# DisplayAddOn_V02-010.net
KiCad netlist of a schematic drawn in EAGLE
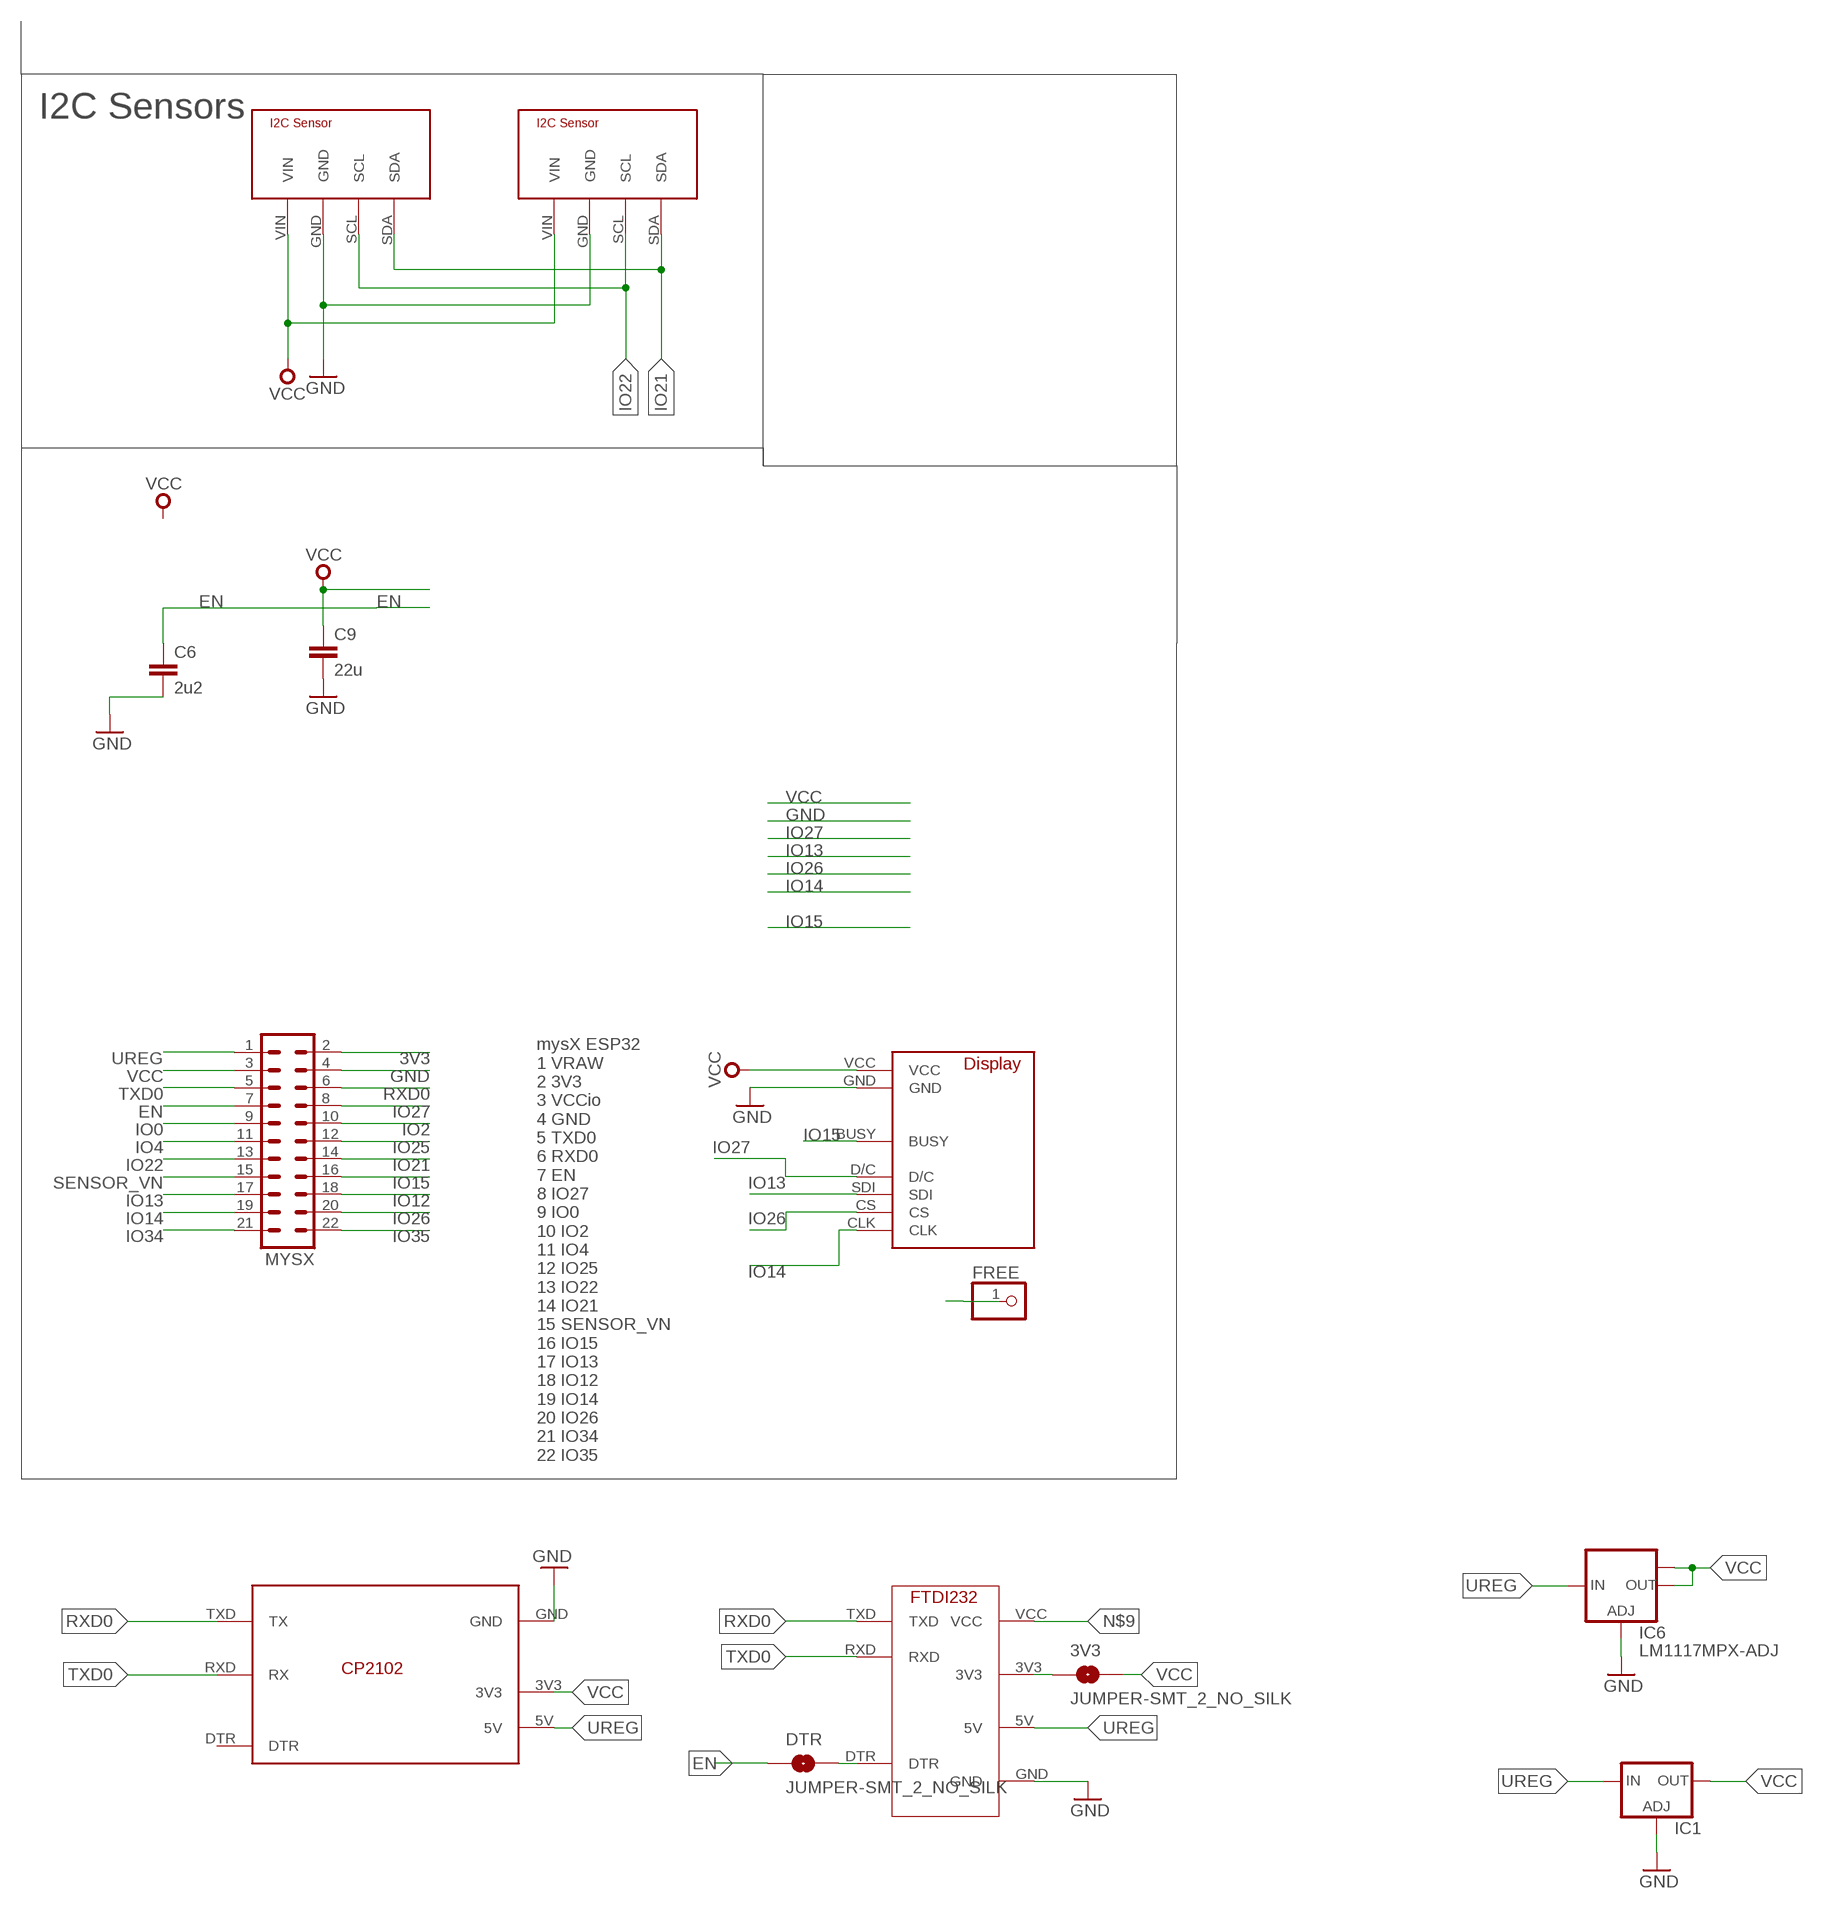
[diagram p0: schematic, sheet 1]

(export (version "E")
  (design (tool "Eeschema 10.0.6"))
  (components
    (comp (ref "3V3")
      (value "JUMPER-SMT_2_NO_SILK")
      (footprint "eagle-import:SMT-JUMPER_2_NO_SILK")
      (libsource (lib "eagle-import") (part "JUMPER-SMT_2_NO_SILK"))
    )
    (comp (ref "C6")
      (value "2u2")
      (footprint "eagle-import:C0805")
      (libsource (lib "eagle-import") (part "C-EUC0805"))
    )
    (comp (ref "C9")
      (value "22u")
      (footprint "eagle-import:C0805")
      (libsource (lib "eagle-import") (part "C-EUC0805"))
    )
    (comp (ref "DTR")
      (value "JUMPER-SMT_2_NO_SILK")
      (footprint "eagle-import:SMT-JUMPER_2_NO_SILK")
      (libsource (lib "eagle-import") (part "JUMPER-SMT_2_NO_SILK"))
    )
    (comp (ref "FREE")
      (value "PINHD-1X1")
      (footprint "eagle-import:1X01")
      (libsource (lib "eagle-import") (part "PINHD-1X1"))
    )
    (comp (ref "HELTEK")
      (value "ZUCZUG_1.54")
      (footprint "eagle-import:ZUCZUG_1.54INCH")
      (libsource (lib "eagle-import") (part "ZUCZUG_1.54"))
    )
    (comp (ref "IC1")
      (value "LD117ADT50TR")
      (footprint "eagle-import:DPACK")
      (libsource (lib "eagle-import") (part "LD117A?DT50TR"))
    )
    (comp (ref "IC6")
      (value "LM1117MPX-ADJ")
      (footprint "eagle-import:SOT223")
      (libsource (lib "eagle-import") (part "LM1117MPX-ADJ"))
    )
    (comp (ref "MYSX")
      (value "MA11-2")
      (footprint "eagle-import:MA11-2")
      (libsource (lib "eagle-import") (part "MA11-2"))
    )
    (comp (ref "U$1")
      (value "CP2101")
      (footprint "eagle-import:CP2101-BEAKOUT")
      (libsource (lib "eagle-import") (part "CP2101"))
    )
    (comp (ref "U$2")
      (value "I2C-BREAKOUT")
      (footprint "eagle-import:I2C_BREAKOUT")
      (libsource (lib "eagle-import") (part "I2C-BREAKOUT"))
    )
    (comp (ref "U$3")
      (value "FTDI232")
      (footprint "eagle-import:FTDI232-LARGE-LESS-PINS")
      (libsource (lib "eagle-import") (part "FTDI232"))
    )
    (comp (ref "U$4")
      (value "I2C-BREAKOUT")
      (footprint "eagle-import:I2C_BREAKOUT")
      (libsource (lib "eagle-import") (part "I2C-BREAKOUT"))
    )
  )
  (nets
    (net (code "1") (name "/3V3") (class "Default")
      (node (ref "MYSX") (pin "2") (pinfunction "2_2") (pintype "passive"))
    )
    (net (code "2") (name "/IO0") (class "Default")
      (node (ref "MYSX") (pin "9") (pinfunction "9_9") (pintype "passive"))
    )
    (net (code "3") (name "/IO2") (class "Default")
      (node (ref "MYSX") (pin "10") (pinfunction "10_10") (pintype "passive"))
    )
    (net (code "4") (name "/IO4") (class "Default")
      (node (ref "MYSX") (pin "11") (pinfunction "11_11") (pintype "passive"))
    )
    (net (code "5") (name "/IO12") (class "Default")
      (node (ref "MYSX") (pin "18") (pinfunction "18_18") (pintype "passive"))
    )
    (net (code "6") (name "/IO13") (class "Default")
      (node (ref "HELTEK") (pin "SDI") (pinfunction "SDI_SDI") (pintype "bidirectional"))
      (node (ref "MYSX") (pin "17") (pinfunction "17_17") (pintype "passive"))
    )
    (net (code "7") (name "/IO14") (class "Default")
      (node (ref "HELTEK") (pin "CLK") (pinfunction "CLK_CLK") (pintype "bidirectional"))
      (node (ref "MYSX") (pin "19") (pinfunction "19_19") (pintype "passive"))
    )
    (net (code "8") (name "/IO15") (class "Default")
      (node (ref "HELTEK") (pin "BUSY") (pinfunction "BUSY_BUSY") (pintype "bidirectional"))
      (node (ref "MYSX") (pin "16") (pinfunction "16_16") (pintype "passive"))
    )
    (net (code "9") (name "/IO25") (class "Default")
      (node (ref "MYSX") (pin "12") (pinfunction "12_12") (pintype "passive"))
    )
    (net (code "10") (name "/IO26") (class "Default")
      (node (ref "HELTEK") (pin "CS") (pinfunction "CS_CS") (pintype "bidirectional"))
      (node (ref "MYSX") (pin "20") (pinfunction "20_20") (pintype "passive"))
    )
    (net (code "11") (name "/IO27") (class "Default")
      (node (ref "HELTEK") (pin "D/C") (pinfunction "D/C_D/C") (pintype "bidirectional"))
      (node (ref "MYSX") (pin "8") (pinfunction "8_8") (pintype "passive"))
    )
    (net (code "12") (name "/IO34") (class "Default")
      (node (ref "MYSX") (pin "21") (pinfunction "21_21") (pintype "passive"))
    )
    (net (code "13") (name "/IO35") (class "Default")
      (node (ref "MYSX") (pin "22") (pinfunction "22_22") (pintype "passive"))
    )
    (net (code "14") (name "/SENSOR_VN") (class "Default")
      (node (ref "MYSX") (pin "15") (pinfunction "15_15") (pintype "passive"))
    )
    (net (code "15") (name "EN") (class "Default")
      (node (ref "C6") (pin "1") (pinfunction "1_1") (pintype "passive"))
      (node (ref "DTR") (pin "1") (pinfunction "1_1") (pintype "passive"))
      (node (ref "MYSX") (pin "7") (pinfunction "7_7") (pintype "passive"))
    )
    (net (code "16") (name "GND") (class "Default")
      (node (ref "C6") (pin "2") (pinfunction "2_2") (pintype "passive"))
      (node (ref "C9") (pin "2") (pinfunction "2_2") (pintype "passive"))
      (node (ref "HELTEK") (pin "GND") (pinfunction "GND_GND") (pintype "power_in"))
      (node (ref "IC1") (pin "1") (pinfunction "ADJ_1") (pintype "input"))
      (node (ref "IC6") (pin "1") (pinfunction "ADJ_1") (pintype "input"))
      (node (ref "MYSX") (pin "4") (pinfunction "4_4") (pintype "passive"))
      (node (ref "U$1") (pin "GND") (pinfunction "GND_GND") (pintype "power_in"))
      (node (ref "U$2") (pin "GND") (pinfunction "GND_GND") (pintype "bidirectional"))
      (node (ref "U$3") (pin "GND") (pinfunction "GND_GND") (pintype "bidirectional"))
      (node (ref "U$4") (pin "GND") (pinfunction "GND_GND") (pintype "bidirectional"))
    )
    (net (code "17") (name "IO21") (class "Default")
      (node (ref "MYSX") (pin "14") (pinfunction "14_14") (pintype "passive"))
      (node (ref "U$2") (pin "SDA") (pinfunction "SDA_SDA") (pintype "bidirectional"))
      (node (ref "U$4") (pin "SDA") (pinfunction "SDA_SDA") (pintype "bidirectional"))
    )
    (net (code "18") (name "IO22") (class "Default")
      (node (ref "MYSX") (pin "13") (pinfunction "13_13") (pintype "passive"))
      (node (ref "U$2") (pin "SCL") (pinfunction "SCL_SCL") (pintype "bidirectional"))
      (node (ref "U$4") (pin "SCL") (pinfunction "SCL_SCL") (pintype "bidirectional"))
    )
    (net (code "19") (name "N$9") (class "Default")
      (node (ref "U$3") (pin "VCC") (pinfunction "VCC_VCC") (pintype "bidirectional"))
    )
    (net (code "20") (name "Net-(3V3-Pad1)") (class "Default")
      (node (ref "3V3") (pin "1") (pinfunction "1_1") (pintype "passive"))
      (node (ref "U$3") (pin "3V3") (pinfunction "3V3_3V3") (pintype "bidirectional"))
    )
    (net (code "21") (name "Net-(DTR-Pad2)") (class "Default")
      (node (ref "DTR") (pin "2") (pinfunction "2_2") (pintype "passive"))
      (node (ref "U$3") (pin "DTR") (pinfunction "DTR_DTR") (pintype "bidirectional"))
    )
    (net (code "22") (name "RXD0") (class "Default")
      (node (ref "MYSX") (pin "6") (pinfunction "6_6") (pintype "passive"))
      (node (ref "U$1") (pin "TXD") (pinfunction "TX_TXD") (pintype "output"))
      (node (ref "U$3") (pin "TXD") (pinfunction "TXD_TXD") (pintype "bidirectional"))
    )
    (net (code "23") (name "TXD0") (class "Default")
      (node (ref "MYSX") (pin "5") (pinfunction "5_5") (pintype "passive"))
      (node (ref "U$1") (pin "RXD") (pinfunction "RX_RXD") (pintype "input"))
      (node (ref "U$3") (pin "RXD") (pinfunction "RXD_RXD") (pintype "bidirectional"))
    )
    (net (code "24") (name "UREG") (class "Default")
      (node (ref "IC1") (pin "3") (pinfunction "IN_3") (pintype "input"))
      (node (ref "IC6") (pin "3") (pinfunction "IN_3") (pintype "input"))
      (node (ref "MYSX") (pin "1") (pinfunction "1_1") (pintype "passive"))
      (node (ref "U$1") (pin "5V") (pinfunction "5V_5V") (pintype "power_in"))
      (node (ref "U$3") (pin "5V") (pinfunction "5V_5V") (pintype "bidirectional"))
    )
    (net (code "25") (name "VCC") (class "Default")
      (node (ref "3V3") (pin "2") (pinfunction "2_2") (pintype "passive"))
      (node (ref "C9") (pin "1") (pinfunction "1_1") (pintype "passive"))
      (node (ref "HELTEK") (pin "VCC") (pinfunction "VCC_VCC") (pintype "power_in"))
      (node (ref "IC1") (pin "4") (pinfunction "OUT_4") (pintype "passive"))
      (node (ref "IC6") (pin "2") (pinfunction "OUT_2") (pintype "passive"))
      (node (ref "IC6") (pin "TAB") (pinfunction "OUT1_TAB") (pintype "passive"))
      (node (ref "MYSX") (pin "3") (pinfunction "3_3") (pintype "passive"))
      (node (ref "U$1") (pin "3V3") (pinfunction "3V3_3V3") (pintype "power_in"))
      (node (ref "U$2") (pin "VIN") (pinfunction "VIN_VIN") (pintype "bidirectional"))
      (node (ref "U$4") (pin "VIN") (pinfunction "VIN_VIN") (pintype "bidirectional"))
    )
    (net (code "26") (name "unconnected-(FREE-Pad1)") (class "Default")
      (node (ref "FREE") (pin "1") (pinfunction "1_1") (pintype "passive"))
    )
    (net (code "27") (name "unconnected-(U$1-PadDTR)") (class "Default")
      (node (ref "U$1") (pin "DTR") (pinfunction "DTR_DTR") (pintype "bidirectional"))
    )
  )
)
